# SPIInterface.net
KiCad netlist of a schematic drawn in Altium Designer
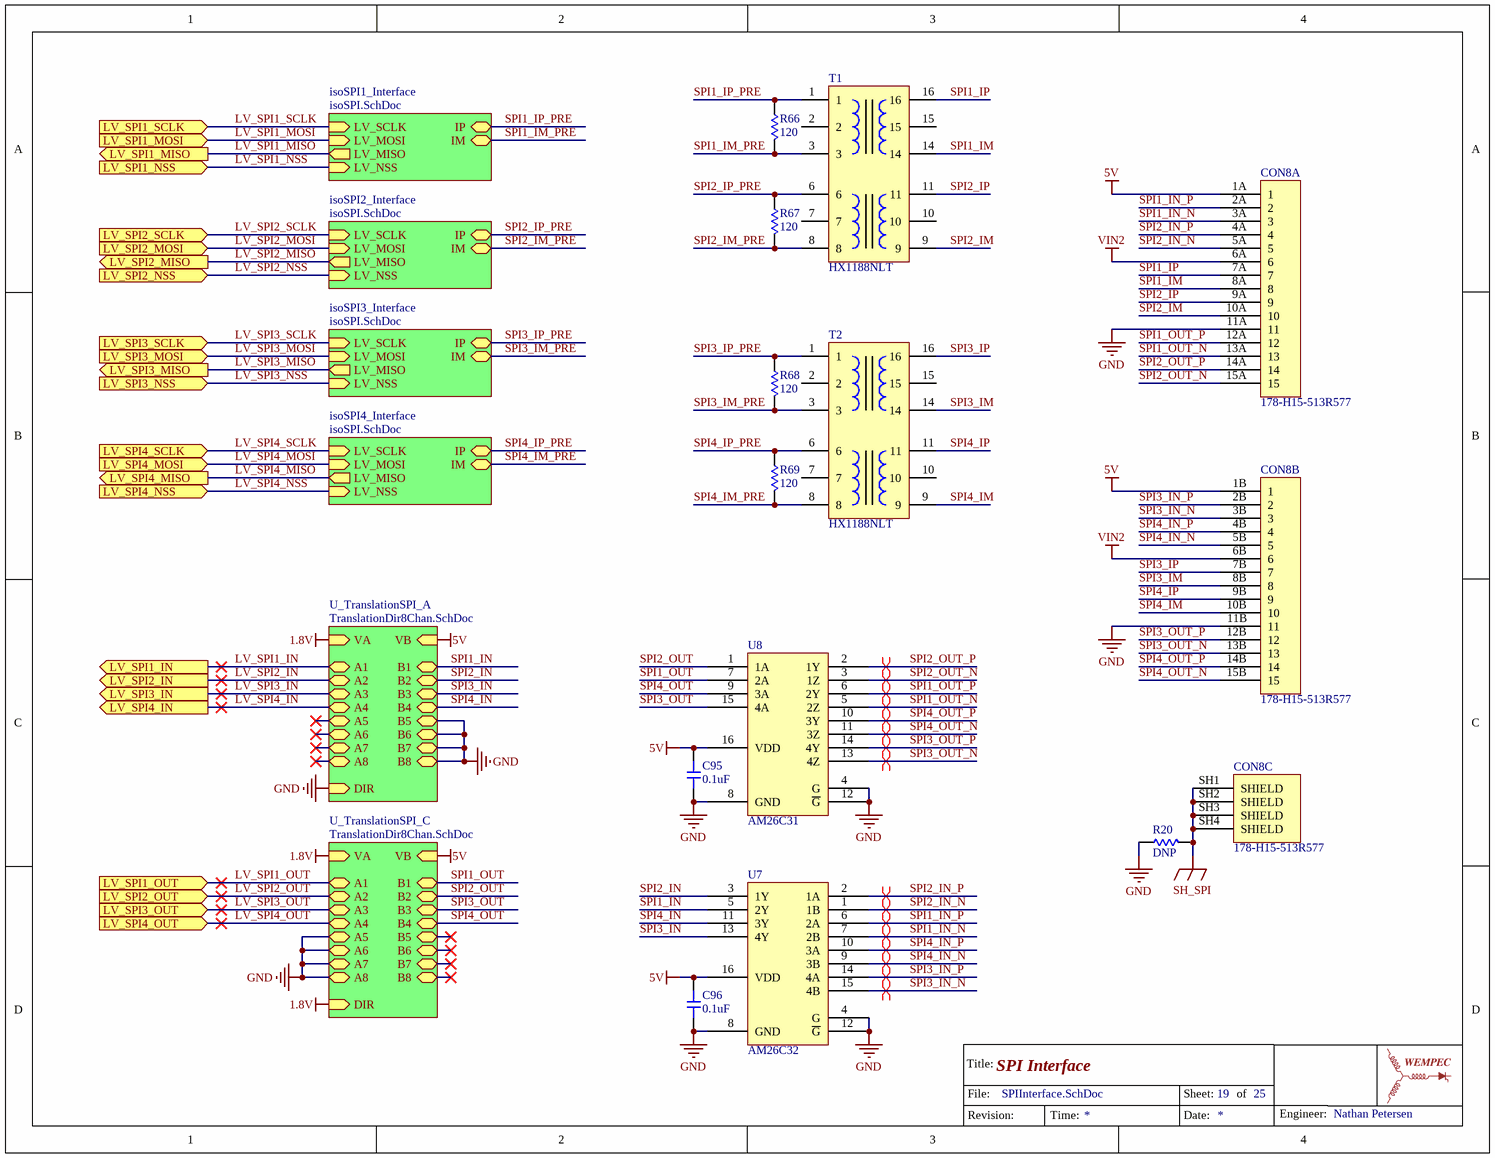
[diagram p0: SPIInterface.SchDoc]

(export (version "E")
  (design (tool "Eeschema 10.0.6"))
  (components
    (comp (ref "C95")
      (value "0.1uF")
      (footprint "0603-CAP")
      (description "Capacitor")
      (libsource (lib "AMDC") (part "Capacitor"))
    )
    (comp (ref "C96")
      (value "0.1uF")
      (footprint "0603-CAP")
      (description "Capacitor")
      (libsource (lib "AMDC") (part "Capacitor"))
    )
    (comp (ref "CON8")
      (value "178-H15-513R577")
      (footprint "178-H15-513R577")
      (description "CONN D-SUB PLUG 15POS R/A SLDR")
      (libsource (lib "AMDC") (part "178-H15-513R577"))
    )
    (comp (ref "R20")
      (value "DNP")
      (footprint "0603-RES")
      (description "Resistor")
      (libsource (lib "AMDC") (part "Resistor"))
    )
    (comp (ref "R66")
      (value "120")
      (footprint "0603-RES")
      (description "Resistor")
      (libsource (lib "AMDC") (part "Resistor"))
    )
    (comp (ref "R67")
      (value "120")
      (footprint "0603-RES")
      (description "Resistor")
      (libsource (lib "AMDC") (part "Resistor"))
    )
    (comp (ref "R68")
      (value "120")
      (footprint "0603-RES")
      (description "Resistor")
      (libsource (lib "AMDC") (part "Resistor"))
    )
    (comp (ref "R69")
      (value "120")
      (footprint "0603-RES")
      (description "Resistor")
      (libsource (lib "AMDC") (part "Resistor"))
    )
    (comp (ref "T1")
      (value "HX1188NLT")
      (footprint "HX1188NLT")
      (description "XFRMR MAGNETIC 1PORT 1:1 10/100")
      (libsource (lib "AMDC") (part "HX1188NLT"))
    )
    (comp (ref "T2")
      (value "HX1188NLT")
      (footprint "HX1188NLT")
      (description "XFRMR MAGNETIC 1PORT 1:1 10/100")
      (libsource (lib "AMDC") (part "HX1188NLT"))
    )
    (comp (ref "U7")
      (value "AM26C32")
      (footprint "TSOP65P640X120-16N")
      (description "IC RCVR RS422 QUAD DIFF 16TSSOP")
      (libsource (lib "AMDC") (part "AM26C32"))
    )
    (comp (ref "U8")
      (value "AM26C31")
      (footprint "TSOP65P640X120-16N")
      (description "IC DRIVER 4/0 16TSSOP")
      (libsource (lib "AMDC") (part "AM26C31"))
    )
  )
  (nets
    (net (code "33") (name "/SPI1_IM") (class "Default")
      (node (ref "CON8") (pin "8A") (pinfunction "8_8A") (pintype "passive"))
      (node (ref "T1") (pin "14") (pinfunction "14_14") (pintype "passive"))
    )
    (net (code "34") (name "/SPI1_IM_PRE") (class "Default")
      (node (ref "R66") (pin "2") (pinfunction "2_2") (pintype "passive"))
      (node (ref "T1") (pin "3") (pinfunction "3_3") (pintype "passive"))
    )
    (net (code "35") (name "/SPI1_IN") (class "Default")
      (node (ref "U7") (pin "5") (pinfunction "2Y_5") (pintype "passive"))
    )
    (net (code "36") (name "/SPI1_IN_N") (class "Default")
      (node (ref "CON8") (pin "3A") (pinfunction "3_3A") (pintype "passive"))
      (node (ref "U7") (pin "7") (pinfunction "2B_7") (pintype "passive"))
    )
    (net (code "37") (name "/SPI1_IN_P") (class "Default")
      (node (ref "CON8") (pin "2A") (pinfunction "2_2A") (pintype "passive"))
      (node (ref "U7") (pin "6") (pinfunction "2A_6") (pintype "passive"))
    )
    (net (code "38") (name "/SPI1_IP") (class "Default")
      (node (ref "CON8") (pin "7A") (pinfunction "7_7A") (pintype "passive"))
      (node (ref "T1") (pin "16") (pinfunction "16_16") (pintype "passive"))
    )
    (net (code "39") (name "/SPI1_IP_PRE") (class "Default")
      (node (ref "R66") (pin "1") (pinfunction "1_1") (pintype "passive"))
      (node (ref "T1") (pin "1") (pinfunction "1_1") (pintype "passive"))
    )
    (net (code "40") (name "/SPI1_OUT") (class "Default")
      (node (ref "U8") (pin "7") (pinfunction "2A_7") (pintype "passive"))
    )
    (net (code "41") (name "/SPI1_OUT_N") (class "Default")
      (node (ref "CON8") (pin "13A") (pinfunction "13_13A") (pintype "passive"))
      (node (ref "U8") (pin "5") (pinfunction "2Z_5") (pintype "passive"))
    )
    (net (code "42") (name "/SPI1_OUT_P") (class "Default")
      (node (ref "CON8") (pin "12A") (pinfunction "12_12A") (pintype "passive"))
      (node (ref "U8") (pin "6") (pinfunction "2Y_6") (pintype "passive"))
    )
    (net (code "43") (name "/SPI2_IM") (class "Default")
      (node (ref "CON8") (pin "10A") (pinfunction "10_10A") (pintype "passive"))
      (node (ref "T1") (pin "9") (pinfunction "9_9") (pintype "passive"))
    )
    (net (code "44") (name "/SPI2_IM_PRE") (class "Default")
      (node (ref "R67") (pin "2") (pinfunction "2_2") (pintype "passive"))
      (node (ref "T1") (pin "8") (pinfunction "8_8") (pintype "passive"))
    )
    (net (code "45") (name "/SPI2_IN") (class "Default")
      (node (ref "U7") (pin "3") (pinfunction "1Y_3") (pintype "passive"))
    )
    (net (code "46") (name "/SPI2_IN_N") (class "Default")
      (node (ref "CON8") (pin "5A") (pinfunction "5_5A") (pintype "passive"))
      (node (ref "U7") (pin "1") (pinfunction "1B_1") (pintype "passive"))
    )
    (net (code "47") (name "/SPI2_IN_P") (class "Default")
      (node (ref "CON8") (pin "4A") (pinfunction "4_4A") (pintype "passive"))
      (node (ref "U7") (pin "2") (pinfunction "1A_2") (pintype "passive"))
    )
    (net (code "48") (name "/SPI2_IP") (class "Default")
      (node (ref "CON8") (pin "9A") (pinfunction "9_9A") (pintype "passive"))
      (node (ref "T1") (pin "11") (pinfunction "11_11") (pintype "passive"))
    )
    (net (code "49") (name "/SPI2_IP_PRE") (class "Default")
      (node (ref "R67") (pin "1") (pinfunction "1_1") (pintype "passive"))
      (node (ref "T1") (pin "6") (pinfunction "6_6") (pintype "passive"))
    )
    (net (code "50") (name "/SPI2_OUT") (class "Default")
      (node (ref "U8") (pin "1") (pinfunction "1A_1") (pintype "passive"))
    )
    (net (code "51") (name "/SPI2_OUT_N") (class "Default")
      (node (ref "CON8") (pin "15A") (pinfunction "15_15A") (pintype "passive"))
      (node (ref "U8") (pin "3") (pinfunction "1Z_3") (pintype "passive"))
    )
    (net (code "52") (name "/SPI2_OUT_P") (class "Default")
      (node (ref "CON8") (pin "14A") (pinfunction "14_14A") (pintype "passive"))
      (node (ref "U8") (pin "2") (pinfunction "1Y_2") (pintype "passive"))
    )
    (net (code "53") (name "/SPI3_IM") (class "Default")
      (node (ref "CON8") (pin "8B") (pinfunction "8_8B") (pintype "passive"))
      (node (ref "T2") (pin "14") (pinfunction "14_14") (pintype "passive"))
    )
    (net (code "54") (name "/SPI3_IM_PRE") (class "Default")
      (node (ref "R68") (pin "2") (pinfunction "2_2") (pintype "passive"))
      (node (ref "T2") (pin "3") (pinfunction "3_3") (pintype "passive"))
    )
    (net (code "55") (name "/SPI3_IN") (class "Default")
      (node (ref "U7") (pin "13") (pinfunction "4Y_13") (pintype "passive"))
    )
    (net (code "56") (name "/SPI3_IN_N") (class "Default")
      (node (ref "CON8") (pin "3B") (pinfunction "3_3B") (pintype "passive"))
      (node (ref "U7") (pin "15") (pinfunction "4B_15") (pintype "passive"))
    )
    (net (code "57") (name "/SPI3_IN_P") (class "Default")
      (node (ref "CON8") (pin "2B") (pinfunction "2_2B") (pintype "passive"))
      (node (ref "U7") (pin "14") (pinfunction "4A_14") (pintype "passive"))
    )
    (net (code "58") (name "/SPI3_IP") (class "Default")
      (node (ref "CON8") (pin "7B") (pinfunction "7_7B") (pintype "passive"))
      (node (ref "T2") (pin "16") (pinfunction "16_16") (pintype "passive"))
    )
    (net (code "59") (name "/SPI3_IP_PRE") (class "Default")
      (node (ref "R68") (pin "1") (pinfunction "1_1") (pintype "passive"))
      (node (ref "T2") (pin "1") (pinfunction "1_1") (pintype "passive"))
    )
    (net (code "60") (name "/SPI3_OUT") (class "Default")
      (node (ref "U8") (pin "15") (pinfunction "4A_15") (pintype "passive"))
    )
    (net (code "61") (name "/SPI3_OUT_N") (class "Default")
      (node (ref "CON8") (pin "13B") (pinfunction "13_13B") (pintype "passive"))
      (node (ref "U8") (pin "13") (pinfunction "4Z_13") (pintype "passive"))
    )
    (net (code "62") (name "/SPI3_OUT_P") (class "Default")
      (node (ref "CON8") (pin "12B") (pinfunction "12_12B") (pintype "passive"))
      (node (ref "U8") (pin "14") (pinfunction "4Y_14") (pintype "passive"))
    )
    (net (code "63") (name "/SPI4_IM") (class "Default")
      (node (ref "CON8") (pin "10B") (pinfunction "10_10B") (pintype "passive"))
      (node (ref "T2") (pin "9") (pinfunction "9_9") (pintype "passive"))
    )
    (net (code "64") (name "/SPI4_IM_PRE") (class "Default")
      (node (ref "R69") (pin "2") (pinfunction "2_2") (pintype "passive"))
      (node (ref "T2") (pin "8") (pinfunction "8_8") (pintype "passive"))
    )
    (net (code "65") (name "/SPI4_IN") (class "Default")
      (node (ref "U7") (pin "11") (pinfunction "3Y_11") (pintype "passive"))
    )
    (net (code "66") (name "/SPI4_IN_N") (class "Default")
      (node (ref "CON8") (pin "5B") (pinfunction "5_5B") (pintype "passive"))
      (node (ref "U7") (pin "9") (pinfunction "3B_9") (pintype "passive"))
    )
    (net (code "67") (name "/SPI4_IN_P") (class "Default")
      (node (ref "CON8") (pin "4B") (pinfunction "4_4B") (pintype "passive"))
      (node (ref "U7") (pin "10") (pinfunction "3A_10") (pintype "passive"))
    )
    (net (code "68") (name "/SPI4_IP") (class "Default")
      (node (ref "CON8") (pin "9B") (pinfunction "9_9B") (pintype "passive"))
      (node (ref "T2") (pin "11") (pinfunction "11_11") (pintype "passive"))
    )
    (net (code "69") (name "/SPI4_IP_PRE") (class "Default")
      (node (ref "R69") (pin "1") (pinfunction "1_1") (pintype "passive"))
      (node (ref "T2") (pin "6") (pinfunction "6_6") (pintype "passive"))
    )
    (net (code "70") (name "/SPI4_OUT") (class "Default")
      (node (ref "U8") (pin "9") (pinfunction "3A_9") (pintype "passive"))
    )
    (net (code "71") (name "/SPI4_OUT_N") (class "Default")
      (node (ref "CON8") (pin "15B") (pinfunction "15_15B") (pintype "passive"))
      (node (ref "U8") (pin "11") (pinfunction "3Z_11") (pintype "passive"))
    )
    (net (code "72") (name "/SPI4_OUT_P") (class "Default")
      (node (ref "CON8") (pin "14B") (pinfunction "14_14B") (pintype "passive"))
      (node (ref "U8") (pin "10") (pinfunction "3Y_10") (pintype "passive"))
    )
    (net (code "74") (name "5V") (class "Default")
      (node (ref "C95") (pin "1") (pinfunction "1_1") (pintype "passive"))
      (node (ref "C96") (pin "1") (pinfunction "1_1") (pintype "passive"))
      (node (ref "CON8") (pin "1A") (pinfunction "1_1A") (pintype "passive"))
      (node (ref "CON8") (pin "1B") (pinfunction "1_1B") (pintype "passive"))
      (node (ref "U7") (pin "16") (pinfunction "VDD_16") (pintype "passive"))
      (node (ref "U8") (pin "16") (pinfunction "VDD_16") (pintype "passive"))
    )
    (net (code "75") (name "GND") (class "Default")
      (node (ref "C95") (pin "2") (pinfunction "2_2") (pintype "passive"))
      (node (ref "C96") (pin "2") (pinfunction "2_2") (pintype "passive"))
      (node (ref "CON8") (pin "11A") (pinfunction "11_11A") (pintype "passive"))
      (node (ref "CON8") (pin "11B") (pinfunction "11_11B") (pintype "passive"))
      (node (ref "R20") (pin "1") (pinfunction "1_1") (pintype "passive"))
      (node (ref "U7") (pin "12") (pinfunction "~{G}_12") (pintype "passive"))
      (node (ref "U7") (pin "4") (pinfunction "G_4") (pintype "passive"))
      (node (ref "U7") (pin "8") (pinfunction "GND_8") (pintype "passive"))
      (node (ref "U8") (pin "12") (pinfunction "~{G}_12") (pintype "passive"))
      (node (ref "U8") (pin "4") (pinfunction "G_4") (pintype "passive"))
      (node (ref "U8") (pin "8") (pinfunction "GND_8") (pintype "passive"))
    )
    (net (code "76") (name "SH_SPI") (class "Default")
      (node (ref "CON8") (pin "SH1") (pinfunction "SHIELD_SH1") (pintype "passive"))
      (node (ref "CON8") (pin "SH2") (pinfunction "SHIELD_SH2") (pintype "passive"))
      (node (ref "CON8") (pin "SH3") (pinfunction "SHIELD_SH3") (pintype "passive"))
      (node (ref "CON8") (pin "SH4") (pinfunction "SHIELD_SH4") (pintype "passive"))
      (node (ref "R20") (pin "2") (pinfunction "2_2") (pintype "passive"))
    )
    (net (code "77") (name "VIN2") (class "Default")
      (node (ref "CON8") (pin "6A") (pinfunction "6_6A") (pintype "passive"))
      (node (ref "CON8") (pin "6B") (pinfunction "6_6B") (pintype "passive"))
    )
    (net (code "78") (name "unconnected-(T1-Pad2)") (class "Default")
      (node (ref "T1") (pin "2") (pinfunction "2_2") (pintype "passive"))
    )
    (net (code "79") (name "unconnected-(T1-Pad7)") (class "Default")
      (node (ref "T1") (pin "7") (pinfunction "7_7") (pintype "passive"))
    )
    (net (code "80") (name "unconnected-(T1-Pad10)") (class "Default")
      (node (ref "T1") (pin "10") (pinfunction "10_10") (pintype "passive"))
    )
    (net (code "81") (name "unconnected-(T1-Pad15)") (class "Default")
      (node (ref "T1") (pin "15") (pinfunction "15_15") (pintype "passive"))
    )
    (net (code "82") (name "unconnected-(T2-Pad2)") (class "Default")
      (node (ref "T2") (pin "2") (pinfunction "2_2") (pintype "passive"))
    )
    (net (code "83") (name "unconnected-(T2-Pad7)") (class "Default")
      (node (ref "T2") (pin "7") (pinfunction "7_7") (pintype "passive"))
    )
    (net (code "84") (name "unconnected-(T2-Pad10)") (class "Default")
      (node (ref "T2") (pin "10") (pinfunction "10_10") (pintype "passive"))
    )
    (net (code "85") (name "unconnected-(T2-Pad15)") (class "Default")
      (node (ref "T2") (pin "15") (pinfunction "15_15") (pintype "passive"))
    )
  )
)
